# SoundChip.net
KiCad netlist of a schematic drawn in Altium Designer
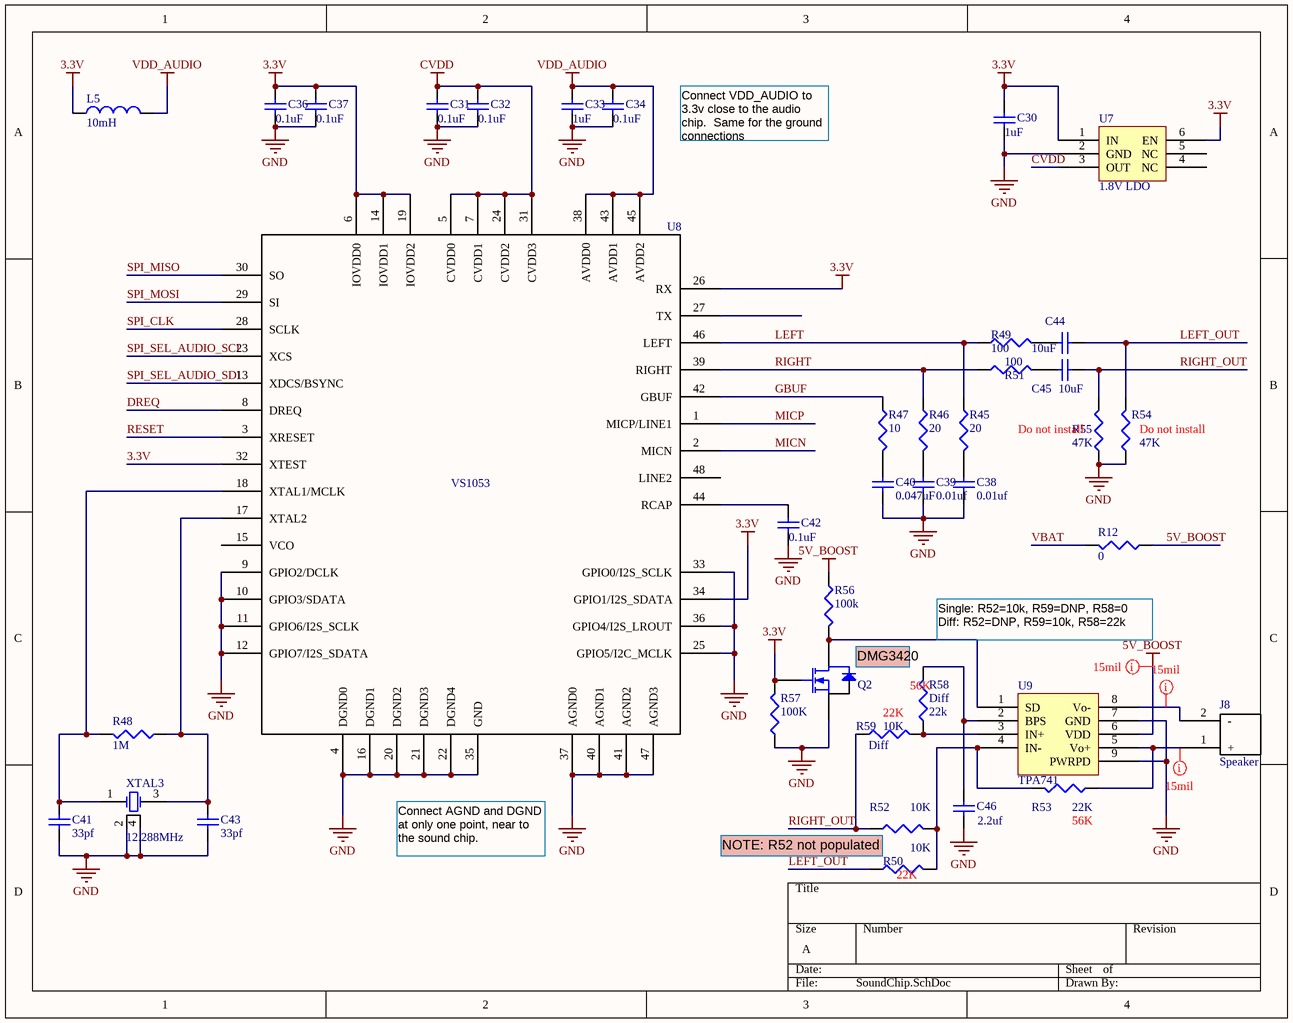
[diagram p0: SoundChip.SchDoc]

(export (version "E")
  (design (tool "Eeschema 10.0.6"))
  (components
    (comp (ref "C30")
      (value "1uF")
      (footprint "CAPC1608L")
      (description "Capacitor (Semiconductor SIM Model)")
      (fields (field (name "Comment") "Cap Semi") (field (name "PUBLISHER") "Altium Limited"))
      (libsource (lib "Miscellaneous Devices") (part "Cap Semi"))
    )
    (comp (ref "C31")
      (value "0.1uF")
      (footprint "CAPC1005L")
      (description "Capacitor (Semiconductor SIM Model)")
      (fields (field (name "Comment") "Cap Semi") (field (name "PUBLISHER") "Altium Limited"))
      (libsource (lib "Miscellaneous Devices") (part "Cap Semi"))
    )
    (comp (ref "C32")
      (value "0.1uF")
      (footprint "CAPC1005L")
      (description "Capacitor (Semiconductor SIM Model)")
      (fields (field (name "Comment") "Cap Semi") (field (name "PUBLISHER") "Altium Limited"))
      (libsource (lib "Miscellaneous Devices") (part "Cap Semi"))
    )
    (comp (ref "C33")
      (value "1uF")
      (footprint "CAPC1608L")
      (description "Capacitor (Semiconductor SIM Model)")
      (fields (field (name "Comment") "Cap Semi") (field (name "PUBLISHER") "Altium Limited"))
      (libsource (lib "Miscellaneous Devices") (part "Cap Semi"))
    )
    (comp (ref "C34")
      (value "0.1uF")
      (footprint "CAPC1005L")
      (description "Capacitor (Semiconductor SIM Model)")
      (fields (field (name "Comment") "Cap Semi") (field (name "PUBLISHER") "Altium Limited"))
      (libsource (lib "Miscellaneous Devices") (part "Cap Semi"))
    )
    (comp (ref "C36")
      (value "0.1uF")
      (footprint "CAPC1005L")
      (description "Capacitor (Semiconductor SIM Model)")
      (fields (field (name "Comment") "Cap Semi") (field (name "PUBLISHER") "Altium Limited"))
      (libsource (lib "Miscellaneous Devices") (part "Cap Semi"))
    )
    (comp (ref "C37")
      (value "0.1uF")
      (footprint "CAPC1005L")
      (description "Capacitor (Semiconductor SIM Model)")
      (fields (field (name "Comment") "Cap Semi") (field (name "PUBLISHER") "Altium Limited"))
      (libsource (lib "Miscellaneous Devices") (part "Cap Semi"))
    )
    (comp (ref "C38")
      (value "0.01uf")
      (footprint "CAPC1005L")
      (description "Capacitor (Semiconductor SIM Model)")
      (fields (field (name "Comment") "Cap Semi") (field (name "PUBLISHER") "Altium Limited"))
      (libsource (lib "Miscellaneous Devices") (part "Cap Semi"))
    )
    (comp (ref "C39")
      (value "0.01uf")
      (footprint "CAPC1005L")
      (description "Capacitor (Semiconductor SIM Model)")
      (fields (field (name "Comment") "Cap Semi") (field (name "PUBLISHER") "Altium Limited"))
      (libsource (lib "Miscellaneous Devices") (part "Cap Semi"))
    )
    (comp (ref "C40")
      (value "0.047uF")
      (footprint "CAPC1005L")
      (description "Capacitor (Semiconductor SIM Model)")
      (fields (field (name "Comment") "Cap Semi") (field (name "PUBLISHER") "Altium Limited"))
      (libsource (lib "Miscellaneous Devices") (part "Cap Semi"))
    )
    (comp (ref "C41")
      (value "33pf")
      (footprint "CAPC1005L")
      (description "Capacitor (Semiconductor SIM Model)")
      (fields (field (name "Comment") "Cap Semi") (field (name "PUBLISHER") "Altium Limited"))
      (libsource (lib "Miscellaneous Devices") (part "Cap Semi"))
    )
    (comp (ref "C42")
      (value "0.1uF")
      (footprint "CAPC1005L")
      (description "Capacitor (Semiconductor SIM Model)")
      (fields (field (name "Comment") "Cap Semi") (field (name "PUBLISHER") "Altium Limited"))
      (libsource (lib "Miscellaneous Devices") (part "Cap Semi"))
    )
    (comp (ref "C43")
      (value "33pf")
      (footprint "CAPC1005L")
      (description "Capacitor (Semiconductor SIM Model)")
      (fields (field (name "Comment") "Cap Semi") (field (name "PUBLISHER") "Altium Limited"))
      (libsource (lib "Miscellaneous Devices") (part "Cap Semi"))
    )
    (comp (ref "C44")
      (value "10uF")
      (footprint "CAPC1608L")
      (description "Capacitor (Semiconductor SIM Model)")
      (fields (field (name "Comment") "Cap Semi") (field (name "PUBLISHER") "Altium Limited"))
      (libsource (lib "Miscellaneous Devices") (part "Cap Semi"))
    )
    (comp (ref "C45")
      (value "10uF")
      (footprint "CAPC1608L")
      (description "Capacitor (Semiconductor SIM Model)")
      (fields (field (name "Comment") "Cap Semi") (field (name "PUBLISHER") "Altium Limited"))
      (libsource (lib "Miscellaneous Devices") (part "Cap Semi"))
    )
    (comp (ref "C46")
      (value "2.2uf")
      (footprint "CAPC1608L")
      (description "Capacitor (Semiconductor SIM Model)")
      (fields (field (name "Comment") "Cap Semi") (field (name "PUBLISHER") "Altium Limited"))
      (libsource (lib "Miscellaneous Devices") (part "Cap Semi"))
    )
    (comp (ref "J8")
      (value "Speaker")
      (footprint "BatteryConnJST")
      (libsource (lib "mrone") (part "BatteryConnJST"))
    )
    (comp (ref "L5")
      (value "10mH")
      (footprint "INDC2012L")
      (description "Inductor")
      (fields (field (name "PUBLISHER") "Altium Limited"))
      (libsource (lib "Miscellaneous Devices") (part "Inductor"))
    )
    (comp (ref "Q2") (value "Mosfet") (footprint "SOT-23") (libsource (lib "mrone") (part "Mosfet")))
    (comp (ref "R12")
      (value "0")
      (footprint "RESC1608L")
      (description "Resistor")
      (fields (field (name "Comment") "Res3") (field (name "PUBLISHER") "Altium Limited"))
      (libsource (lib "Miscellaneous Devices") (part "Res3"))
    )
    (comp (ref "R45")
      (value "20")
      (footprint "RESC1608L")
      (description "Resistor")
      (fields (field (name "Comment") "Res3") (field (name "PUBLISHER") "Altium Limited"))
      (libsource (lib "Miscellaneous Devices") (part "Res3"))
    )
    (comp (ref "R46")
      (value "20")
      (footprint "RESC1608L")
      (description "Resistor")
      (fields (field (name "Comment") "Res3") (field (name "PUBLISHER") "Altium Limited"))
      (libsource (lib "Miscellaneous Devices") (part "Res3"))
    )
    (comp (ref "R47")
      (value "10")
      (footprint "RESC1608L")
      (description "Resistor")
      (fields (field (name "Comment") "Res3") (field (name "PUBLISHER") "Altium Limited"))
      (libsource (lib "Miscellaneous Devices") (part "Res3"))
    )
    (comp (ref "R48")
      (value "1M")
      (footprint "RESC1608L")
      (description "Resistor")
      (fields (field (name "Comment") "Res3") (field (name "PUBLISHER") "Altium Limited"))
      (libsource (lib "Miscellaneous Devices") (part "Res3"))
    )
    (comp (ref "R49")
      (value "100")
      (footprint "RESC1608L")
      (description "Resistor")
      (fields (field (name "Comment") "Res3") (field (name "PUBLISHER") "Altium Limited"))
      (libsource (lib "Miscellaneous Devices") (part "Res3"))
    )
    (comp (ref "R50")
      (value "10K")
      (footprint "RESC1608L")
      (description "Resistor")
      (fields (field (name "Comment") "Res3") (field (name "PUBLISHER") "Altium Limited"))
      (libsource (lib "Miscellaneous Devices") (part "Res3"))
    )
    (comp (ref "R51")
      (value "100")
      (footprint "RESC1608L")
      (description "Resistor")
      (fields (field (name "Comment") "Res3") (field (name "PUBLISHER") "Altium Limited"))
      (libsource (lib "Miscellaneous Devices") (part "Res3"))
    )
    (comp (ref "R52")
      (value "10K")
      (footprint "RESC1608L")
      (description "Resistor")
      (fields (field (name "Comment") "Res3") (field (name "PUBLISHER") "Altium Limited"))
      (libsource (lib "Miscellaneous Devices") (part "Res3"))
    )
    (comp (ref "R53")
      (value "22K")
      (footprint "RESC1608L")
      (description "Resistor")
      (fields (field (name "Comment") "Res3") (field (name "PUBLISHER") "Altium Limited"))
      (libsource (lib "Miscellaneous Devices") (part "Res3"))
    )
    (comp (ref "R54")
      (value "47K")
      (footprint "RESC1608L")
      (description "Resistor")
      (fields (field (name "Comment") "Res3") (field (name "PUBLISHER") "Altium Limited"))
      (libsource (lib "Miscellaneous Devices") (part "Res3"))
    )
    (comp (ref "R55")
      (value "47K")
      (footprint "RESC1608L")
      (description "Resistor")
      (fields (field (name "Comment") "Res3") (field (name "PUBLISHER") "Altium Limited"))
      (libsource (lib "Miscellaneous Devices") (part "Res3"))
    )
    (comp (ref "R56")
      (value "100k")
      (footprint "RESC1608L")
      (description "Resistor")
      (fields (field (name "Comment") "Res3") (field (name "PUBLISHER") "Altium Limited"))
      (libsource (lib "Miscellaneous Devices") (part "Res3"))
    )
    (comp (ref "R57")
      (value "100K")
      (footprint "RESC1608L")
      (description "Resistor")
      (fields (field (name "Comment") "Res3") (field (name "PUBLISHER") "Altium Limited"))
      (libsource (lib "Miscellaneous Devices") (part "Res3"))
    )
    (comp (ref "R58")
      (value "Diff")
      (footprint "RESC1608L")
      (description "Resistor")
      (fields (field (name "ALTIUM_VALUE") "22k") (field (name "PUBLISHER") "Altium Limited"))
      (libsource (lib "Miscellaneous Devices") (part "Res3"))
    )
    (comp (ref "R59")
      (value "Diff")
      (footprint "RESC1608L")
      (description "Resistor")
      (fields (field (name "ALTIUM_VALUE") "10K") (field (name "PUBLISHER") "Altium Limited"))
      (libsource (lib "Miscellaneous Devices") (part "Res3"))
    )
    (comp (ref "U7") (value "1.8V LDO") (footprint "WFDFN-6") (libsource (lib "mrone") (part "1.8V_LDO")))
    (comp (ref "U8") (value "VS1053") (footprint "LQFP-48") (libsource (lib "mrone") (part "VS1053")))
    (comp (ref "U9")
      (value "TPA741")
      (footprint "audio amp")
      (libsource (lib "mrone") (part "Audio Amp TPA741"))
    )
    (comp (ref "XTAL3") (value "12.288MHz") (footprint "CRYSTAL") (libsource (lib "mrone") (part "Crystal")))
  )
  (nets
    (net (code "1") (name "/DREQ") (class "Default")
      (node (ref "U8") (pin "8") (pinfunction "DREQ_8") (pintype "passive"))
    )
    (net (code "2") (name "/GBUF") (class "Default")
      (node (ref "R47") (pin "1") (pinfunction "1_1") (pintype "passive"))
      (node (ref "U8") (pin "42") (pinfunction "GBUF_42") (pintype "passive"))
    )
    (net (code "3") (name "/LEFT") (class "Default")
      (node (ref "R45") (pin "1") (pinfunction "1_1") (pintype "passive"))
      (node (ref "R49") (pin "1") (pinfunction "1_1") (pintype "passive"))
      (node (ref "U8") (pin "46") (pinfunction "LEFT_46") (pintype "passive"))
    )
    (net (code "4") (name "/LEFT_OUT") (class "Default")
      (node (ref "C44") (pin "1") (pinfunction "1_1") (pintype "passive"))
      (node (ref "R50") (pin "1") (pinfunction "1_1") (pintype "passive"))
      (node (ref "R54") (pin "2") (pinfunction "2_2") (pintype "passive"))
    )
    (net (code "5") (name "/MICN") (class "Default")
      (node (ref "U8") (pin "2") (pinfunction "MICN_2") (pintype "passive"))
    )
    (net (code "6") (name "/MICP") (class "Default")
      (node (ref "U8") (pin "1") (pinfunction "MICP/LINE1_1") (pintype "passive"))
    )
    (net (code "7") (name "/RESET") (class "Default")
      (node (ref "U8") (pin "3") (pinfunction "XRESET_3") (pintype "passive"))
    )
    (net (code "8") (name "/RIGHT") (class "Default")
      (node (ref "R46") (pin "1") (pinfunction "1_1") (pintype "passive"))
      (node (ref "R51") (pin "1") (pinfunction "1_1") (pintype "passive"))
      (node (ref "U8") (pin "39") (pinfunction "RIGHT_39") (pintype "passive"))
    )
    (net (code "9") (name "/RIGHT_OUT") (class "Default")
      (node (ref "C45") (pin "1") (pinfunction "1_1") (pintype "passive"))
      (node (ref "R52") (pin "1") (pinfunction "1_1") (pintype "passive"))
      (node (ref "R55") (pin "2") (pinfunction "2_2") (pintype "passive"))
      (node (ref "R59") (pin "1") (pinfunction "1_1") (pintype "passive"))
    )
    (net (code "10") (name "/SPI_CLK") (class "Default")
      (node (ref "U8") (pin "28") (pinfunction "SCLK_28") (pintype "passive"))
    )
    (net (code "11") (name "/SPI_MISO") (class "Default")
      (node (ref "U8") (pin "30") (pinfunction "SO_30") (pintype "passive"))
    )
    (net (code "12") (name "/SPI_MOSI") (class "Default")
      (node (ref "U8") (pin "29") (pinfunction "SI_29") (pintype "passive"))
    )
    (net (code "13") (name "/SPI_SEL_AUDIO_SCI") (class "Default")
      (node (ref "U8") (pin "23") (pinfunction "XCS_23") (pintype "passive"))
    )
    (net (code "14") (name "/SPI_SEL_AUDIO_SDI") (class "Default")
      (node (ref "U8") (pin "13") (pinfunction "XDCS/BSYNC_13") (pintype "passive"))
    )
    (net (code "15") (name "/VBAT") (class "Default")
      (node (ref "R12") (pin "2") (pinfunction "2_2") (pintype "passive"))
    )
    (net (code "16") (name "3.3V") (class "Default")
      (node (ref "C30") (pin "1") (pinfunction "1_1") (pintype "passive"))
      (node (ref "C36") (pin "2") (pinfunction "2_2") (pintype "passive"))
      (node (ref "C37") (pin "2") (pinfunction "2_2") (pintype "passive"))
      (node (ref "L5") (pin "2") (pinfunction "2_2") (pintype "passive"))
      (node (ref "Q2") (pin "1") (pinfunction "G_1") (pintype "passive"))
      (node (ref "R57") (pin "2") (pinfunction "2_2") (pintype "passive"))
      (node (ref "U7") (pin "1") (pinfunction "IN_1") (pintype "passive"))
      (node (ref "U7") (pin "6") (pinfunction "EN_6") (pintype "passive"))
      (node (ref "U8") (pin "14") (pinfunction "IOVDD1_14") (pintype "passive"))
      (node (ref "U8") (pin "19") (pinfunction "IOVDD2_19") (pintype "passive"))
      (node (ref "U8") (pin "26") (pinfunction "RX_26") (pintype "passive"))
      (node (ref "U8") (pin "32") (pinfunction "XTEST_32") (pintype "passive"))
      (node (ref "U8") (pin "34") (pinfunction "GPIO1/I2S_SDATA_34") (pintype "passive"))
      (node (ref "U8") (pin "6") (pinfunction "IOVDD0_6") (pintype "passive"))
    )
    (net (code "17") (name "5V_BOOST") (class "Default")
      (node (ref "R12") (pin "1") (pinfunction "1_1") (pintype "passive"))
      (node (ref "R56") (pin "2") (pinfunction "2_2") (pintype "passive"))
      (node (ref "U9") (pin "6") (pinfunction "VDD_6") (pintype "passive"))
    )
    (net (code "18") (name "CVDD") (class "Default")
      (node (ref "C31") (pin "2") (pinfunction "2_2") (pintype "passive"))
      (node (ref "C32") (pin "2") (pinfunction "2_2") (pintype "passive"))
      (node (ref "U7") (pin "3") (pinfunction "OUT_3") (pintype "passive"))
      (node (ref "U8") (pin "24") (pinfunction "CVDD2_24") (pintype "passive"))
      (node (ref "U8") (pin "31") (pinfunction "CVDD3_31") (pintype "passive"))
      (node (ref "U8") (pin "5") (pinfunction "CVDD0_5") (pintype "passive"))
      (node (ref "U8") (pin "7") (pinfunction "CVDD1_7") (pintype "passive"))
    )
    (net (code "19") (name "GND") (class "Default")
      (node (ref "C30") (pin "2") (pinfunction "2_2") (pintype "passive"))
      (node (ref "C31") (pin "1") (pinfunction "1_1") (pintype "passive"))
      (node (ref "C32") (pin "1") (pinfunction "1_1") (pintype "passive"))
      (node (ref "C33") (pin "2") (pinfunction "2_2") (pintype "passive"))
      (node (ref "C34") (pin "1") (pinfunction "1_1") (pintype "passive"))
      (node (ref "C36") (pin "1") (pinfunction "1_1") (pintype "passive"))
      (node (ref "C37") (pin "1") (pinfunction "1_1") (pintype "passive"))
      (node (ref "C38") (pin "2") (pinfunction "2_2") (pintype "passive"))
      (node (ref "C39") (pin "2") (pinfunction "2_2") (pintype "passive"))
      (node (ref "C40") (pin "2") (pinfunction "2_2") (pintype "passive"))
      (node (ref "C41") (pin "2") (pinfunction "2_2") (pintype "passive"))
      (node (ref "C42") (pin "1") (pinfunction "1_1") (pintype "passive"))
      (node (ref "C43") (pin "2") (pinfunction "2_2") (pintype "passive"))
      (node (ref "C46") (pin "1") (pinfunction "1_1") (pintype "passive"))
      (node (ref "Q2") (pin "2") (pinfunction "S_2") (pintype "passive"))
      (node (ref "R54") (pin "1") (pinfunction "1_1") (pintype "passive"))
      (node (ref "R55") (pin "1") (pinfunction "1_1") (pintype "passive"))
      (node (ref "R57") (pin "1") (pinfunction "1_1") (pintype "passive"))
      (node (ref "U7") (pin "2") (pinfunction "GND_2") (pintype "passive"))
      (node (ref "U8") (pin "10") (pinfunction "GPIO3/SDATA_10") (pintype "passive"))
      (node (ref "U8") (pin "11") (pinfunction "GPIO6/I2S_SCLK_11") (pintype "passive"))
      (node (ref "U8") (pin "12") (pinfunction "GPIO7/I2S_SDATA_12") (pintype "passive"))
      (node (ref "U8") (pin "16") (pinfunction "DGND1_16") (pintype "passive"))
      (node (ref "U8") (pin "20") (pinfunction "DGND2_20") (pintype "passive"))
      (node (ref "U8") (pin "21") (pinfunction "DGND3_21") (pintype "passive"))
      (node (ref "U8") (pin "22") (pinfunction "DGND4_22") (pintype "passive"))
      (node (ref "U8") (pin "25") (pinfunction "GPIO5/I2C_MCLK_25") (pintype "passive"))
      (node (ref "U8") (pin "33") (pinfunction "GPIO0/I2S_SCLK_33") (pintype "passive"))
      (node (ref "U8") (pin "35") (pinfunction "GND_35") (pintype "passive"))
      (node (ref "U8") (pin "36") (pinfunction "GPIO4/I2S_LROUT_36") (pintype "passive"))
      (node (ref "U8") (pin "37") (pinfunction "AGND0_37") (pintype "passive"))
      (node (ref "U8") (pin "4") (pinfunction "DGND0_4") (pintype "passive"))
      (node (ref "U8") (pin "40") (pinfunction "AGND1_40") (pintype "passive"))
      (node (ref "U8") (pin "41") (pinfunction "AGND2_41") (pintype "passive"))
      (node (ref "U8") (pin "47") (pinfunction "AGND3_47") (pintype "passive"))
      (node (ref "U8") (pin "9") (pinfunction "GPIO2/DCLK_9") (pintype "passive"))
      (node (ref "U9") (pin "7") (pinfunction "GND_7") (pintype "passive"))
      (node (ref "U9") (pin "9") (pinfunction "PWRPD_9") (pintype "passive"))
      (node (ref "XTAL3") (pin "2") (pinfunction "GND_2") (pintype "passive"))
      (node (ref "XTAL3") (pin "4") (pinfunction "GND_4") (pintype "passive"))
    )
    (net (code "20") (name "Net-(C38-Pad1)") (class "Default")
      (node (ref "C38") (pin "1") (pinfunction "1_1") (pintype "passive"))
      (node (ref "R45") (pin "2") (pinfunction "2_2") (pintype "passive"))
    )
    (net (code "21") (name "Net-(C39-Pad1)") (class "Default")
      (node (ref "C39") (pin "1") (pinfunction "1_1") (pintype "passive"))
      (node (ref "R46") (pin "2") (pinfunction "2_2") (pintype "passive"))
    )
    (net (code "22") (name "Net-(C40-Pad1)") (class "Default")
      (node (ref "C40") (pin "1") (pinfunction "1_1") (pintype "passive"))
      (node (ref "R47") (pin "2") (pinfunction "2_2") (pintype "passive"))
    )
    (net (code "23") (name "Net-(C44-Pad2)") (class "Default")
      (node (ref "C44") (pin "2") (pinfunction "2_2") (pintype "passive"))
      (node (ref "R49") (pin "2") (pinfunction "2_2") (pintype "passive"))
    )
    (net (code "24") (name "Net-(C45-Pad2)") (class "Default")
      (node (ref "C45") (pin "2") (pinfunction "2_2") (pintype "passive"))
      (node (ref "R51") (pin "2") (pinfunction "2_2") (pintype "passive"))
    )
    (net (code "25") (name "Net-(J8-+)") (class "Default")
      (node (ref "J8") (pin "1") (pinfunction "+_1") (pintype "passive"))
      (node (ref "R53") (pin "1") (pinfunction "1_1") (pintype "passive"))
      (node (ref "U9") (pin "5") (pinfunction "Vo+_5") (pintype "passive"))
    )
    (net (code "26") (name "Net-(J8--)") (class "Default")
      (node (ref "J8") (pin "2") (pinfunction "-_2") (pintype "passive"))
      (node (ref "U9") (pin "8") (pinfunction "Vo-_8") (pintype "passive"))
    )
    (net (code "27") (name "Net-(Q2-D)") (class "Default")
      (node (ref "Q2") (pin "3") (pinfunction "D_3") (pintype "passive"))
      (node (ref "R56") (pin "1") (pinfunction "1_1") (pintype "passive"))
      (node (ref "U9") (pin "1") (pinfunction "SD_1") (pintype "passive"))
    )
    (net (code "28") (name "Net-(U8-RCAP)") (class "Default")
      (node (ref "C42") (pin "2") (pinfunction "2_2") (pintype "passive"))
      (node (ref "U8") (pin "44") (pinfunction "RCAP_44") (pintype "passive"))
    )
    (net (code "29") (name "Net-(U8-XTAL1{slash}MCLK)") (class "Default")
      (node (ref "C41") (pin "1") (pinfunction "1_1") (pintype "passive"))
      (node (ref "R48") (pin "2") (pinfunction "2_2") (pintype "passive"))
      (node (ref "U8") (pin "18") (pinfunction "XTAL1/MCLK_18") (pintype "passive"))
      (node (ref "XTAL3") (pin "1") (pinfunction "OSC1_1") (pintype "passive"))
    )
    (net (code "30") (name "Net-(U8-XTAL2)") (class "Default")
      (node (ref "C43") (pin "1") (pinfunction "1_1") (pintype "passive"))
      (node (ref "R48") (pin "1") (pinfunction "1_1") (pintype "passive"))
      (node (ref "U8") (pin "17") (pinfunction "XTAL2_17") (pintype "passive"))
      (node (ref "XTAL3") (pin "3") (pinfunction "OSC2_3") (pintype "passive"))
    )
    (net (code "31") (name "Net-(U9-BPS)") (class "Default")
      (node (ref "C46") (pin "2") (pinfunction "2_2") (pintype "passive"))
      (node (ref "R58") (pin "2") (pinfunction "2_2") (pintype "passive"))
      (node (ref "U9") (pin "2") (pinfunction "BPS_2") (pintype "passive"))
    )
    (net (code "32") (name "Net-(U9-IN+)") (class "Default")
      (node (ref "R58") (pin "1") (pinfunction "1_1") (pintype "passive"))
      (node (ref "R59") (pin "2") (pinfunction "2_2") (pintype "passive"))
      (node (ref "U9") (pin "3") (pinfunction "IN+_3") (pintype "passive"))
    )
    (net (code "33") (name "Net-(U9-IN-)") (class "Default")
      (node (ref "R50") (pin "2") (pinfunction "2_2") (pintype "passive"))
      (node (ref "R52") (pin "2") (pinfunction "2_2") (pintype "passive"))
      (node (ref "R53") (pin "2") (pinfunction "2_2") (pintype "passive"))
      (node (ref "U9") (pin "4") (pinfunction "IN-_4") (pintype "passive"))
    )
    (net (code "34") (name "VDD_AUDIO") (class "Default")
      (node (ref "C33") (pin "1") (pinfunction "1_1") (pintype "passive"))
      (node (ref "C34") (pin "2") (pinfunction "2_2") (pintype "passive"))
      (node (ref "L5") (pin "1") (pinfunction "1_1") (pintype "passive"))
      (node (ref "U8") (pin "38") (pinfunction "AVDD0_38") (pintype "passive"))
      (node (ref "U8") (pin "43") (pinfunction "AVDD1_43") (pintype "passive"))
      (node (ref "U8") (pin "45") (pinfunction "AVDD2_45") (pintype "passive"))
    )
    (net (code "35") (name "unconnected-(U7-NC-Pad4)") (class "Default")
      (node (ref "U7") (pin "4") (pinfunction "NC_4") (pintype "passive"))
    )
    (net (code "36") (name "unconnected-(U7-NC-Pad5)") (class "Default")
      (node (ref "U7") (pin "5") (pinfunction "NC_5") (pintype "passive"))
    )
    (net (code "37") (name "unconnected-(U8-LINE2-Pad48)") (class "Default")
      (node (ref "U8") (pin "48") (pinfunction "LINE2_48") (pintype "passive"))
    )
    (net (code "38") (name "unconnected-(U8-TX-Pad27)") (class "Default")
      (node (ref "U8") (pin "27") (pinfunction "TX_27") (pintype "passive"))
    )
    (net (code "39") (name "unconnected-(U8-VCO-Pad15)") (class "Default")
      (node (ref "U8") (pin "15") (pinfunction "VCO_15") (pintype "passive"))
    )
  )
)
